# Power_supply.net
KiCad netlist of a schematic drawn in Altium Designer
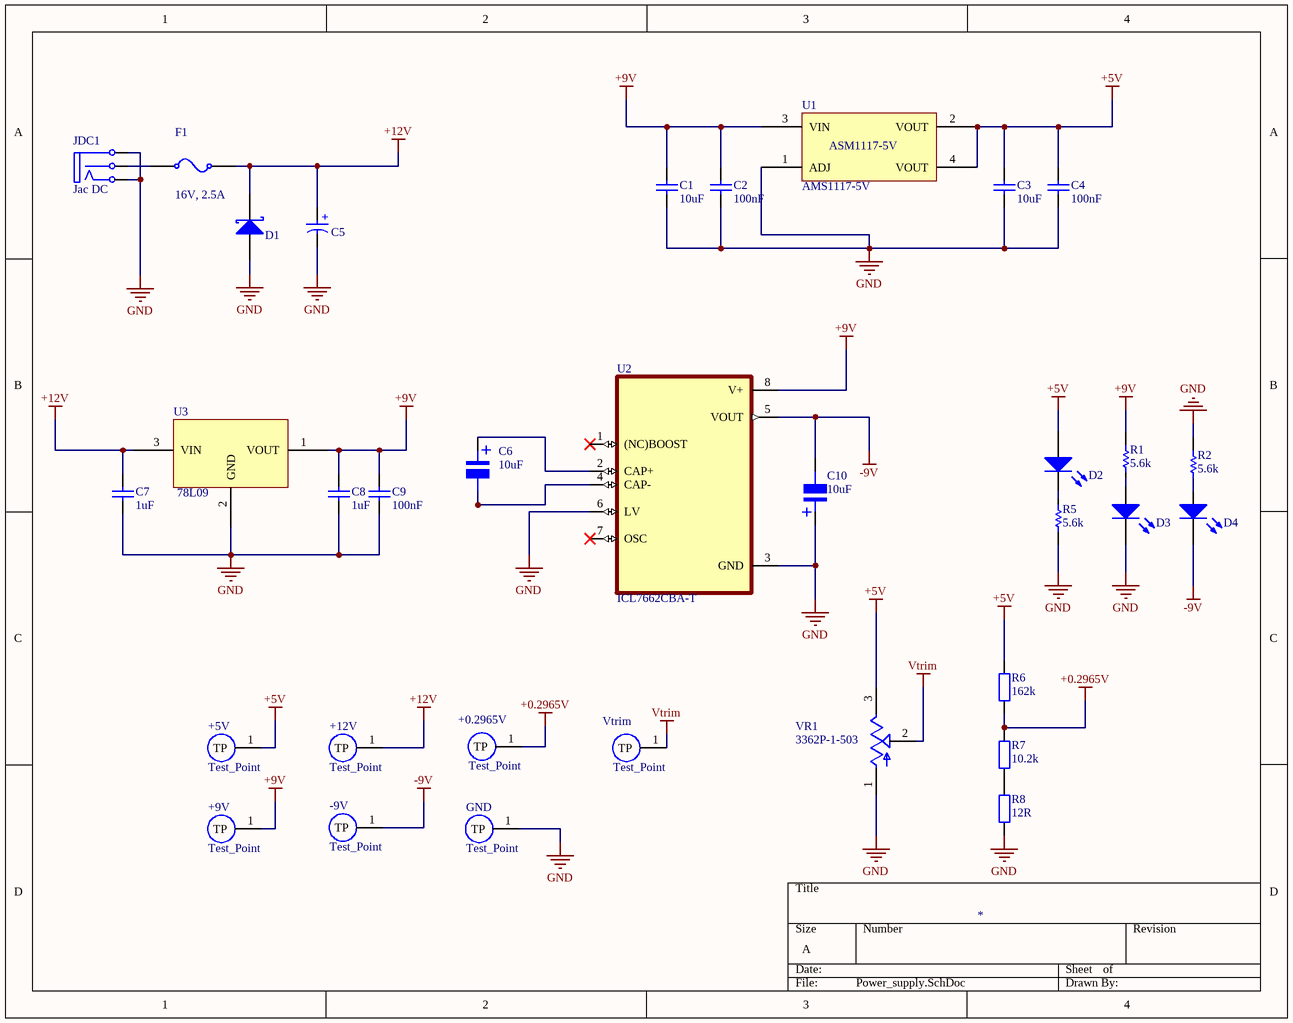
[diagram p0: Power_supply.SchDoc]

(export (version "E")
  (design (tool "Eeschema 10.0.6"))
  (components
    (comp (ref "+0.2965V")
      (value "Test_Point")
      (footprint "TP_2MM")
      (description "Test point, 2mm radius")
      (libsource (lib "SMIOT_Lib_Schematic") (part "Test_Point"))
    )
    (comp (ref "+5V")
      (value "Test_Point")
      (footprint "TP_2MM")
      (description "Test point, 2mm radius")
      (libsource (lib "SMIOT_Lib_Schematic") (part "Test_Point"))
    )
    (comp (ref "+9V")
      (value "Test_Point")
      (footprint "TP_2MM")
      (description "Test point, 2mm radius")
      (libsource (lib "SMIOT_Lib_Schematic") (part "Test_Point"))
    )
    (comp (ref "+12V")
      (value "Test_Point")
      (footprint "TP_2MM")
      (description "Test point, 2mm radius")
      (libsource (lib "SMIOT_Lib_Schematic") (part "Test_Point"))
    )
    (comp (ref "-9V")
      (value "Test_Point")
      (footprint "TP_2MM")
      (description "Test point, 2mm radius")
      (libsource (lib "SMIOT_Lib_Schematic") (part "Test_Point"))
    )
    (comp (ref "C1")
      (value "10uF")
      (footprint "CAP_0603")
      (description "CAP, size 0603,10uF")
      (libsource (lib "SMIOT_Lib_Schematic") (part "01060310010"))
    )
    (comp (ref "C2")
      (value "100nF")
      (footprint "CAP_0603")
      (description "CAP, size 0603, 100nF")
      (libsource (lib "SMIOT_Lib_Schematic") (part "01060310410"))
    )
    (comp (ref "C3")
      (value "10uF")
      (footprint "CAP_0603")
      (description "CAP, size 0603,10uF")
      (libsource (lib "SMIOT_Lib_Schematic") (part "01060310010"))
    )
    (comp (ref "C4")
      (value "100nF")
      (footprint "CAP_0603")
      (description "CAP, size 0603, 100nF")
      (libsource (lib "SMIOT_Lib_Schematic") (part "01060310410"))
    )
    (comp (ref "C5")
      (value "22uF")
      (footprint "WCAP-ASLI_D4H5.5")
      (description "V-Chip, D4 x H5.5mm, 22uF, 16V")
      (libsource (lib "SMIOT_Lib_Schematic") (part "865080340003"))
    )
    (comp (ref "C6")
      (value "10uF")
      (footprint "tu nhom 4 (b)")
      (description "Dán")
      (libsource (lib "") (part "Tu Nhom 10uF 16V_1"))
    )
    (comp (ref "C7")
      (value "1uF")
      (footprint "CAP_0603")
      (description "CAP, size 0603, 1uF")
      (libsource (lib "SMIOT_Lib_Schematic") (part "01060310510"))
    )
    (comp (ref "C8")
      (value "1uF")
      (footprint "CAP_0603")
      (description "CAP, size 0603, 1uF")
      (libsource (lib "SMIOT_Lib_Schematic") (part "01060310510"))
    )
    (comp (ref "C9")
      (value "100nF")
      (footprint "CAP_0603")
      (description "CAP, size 0603, 100nF")
      (libsource (lib "SMIOT_Lib_Schematic") (part "01060310410"))
    )
    (comp (ref "C10")
      (value "10uF")
      (footprint "tu nhom 4 (b)")
      (description "Dán")
      (libsource (lib "Tu dien") (part "Tu Nhom 10uF 16V"))
    )
    (comp (ref "D1")
      (value "D Schottky")
      (footprint "SS34")
      (description "Schottky Diode")
      (fields (field (name "PUBLISHER") "Altium Limited"))
      (libsource (lib "SMIOT_Lib_Schematic") (part "D Schottky"))
    )
    (comp (ref "D2")
      (value "LED SMD")
      (footprint "LED_0805_Blue")
      (description "LED")
      (libsource (lib "SMIOT_Lib_Schematic") (part "LED SMD"))
    )
    (comp (ref "D3")
      (value "LED SMD")
      (footprint "LED_0805_Blue")
      (description "LED")
      (libsource (lib "SMIOT_Lib_Schematic") (part "LED SMD"))
    )
    (comp (ref "D4")
      (value "LED SMD")
      (footprint "LED_0805_Blue")
      (description "LED")
      (libsource (lib "SMIOT_Lib_Schematic") (part "LED SMD"))
    )
    (comp (ref "F1")
      (value "16V, 2.5A")
      (footprint "Fuse_SMD_1812")
      (description "Resettable Fuse, Size 1812, 8V, 2A")
      (fields (field (name "MANUFACTURER") "Littelfuse"))
      (libsource (lib "SMIOT_Lib_Schematic") (part "061812200008"))
    )
    (comp (ref "GND")
      (value "Test_Point")
      (footprint "TP_2MM")
      (description "Test point, 2mm radius")
      (libsource (lib "SMIOT_Lib_Schematic") (part "Test_Point"))
    )
    (comp (ref "JDC1")
      (value "Jac DC")
      (footprint "DC0")
      (description "Jac DC input")
      (libsource (lib "Library") (part "DCIN"))
    )
    (comp (ref "R1")
      (value "5.6k")
      (footprint "resistor_0603")
      (description "RES, 5.6k Ohm, size 0603, 1%")
      (libsource (lib "SMIOT_Lib_Schematic") (part "0006035621"))
    )
    (comp (ref "R2")
      (value "5.6k")
      (footprint "resistor_0603")
      (description "RES, 5.6k Ohm, size 0603, 1%")
      (libsource (lib "SMIOT_Lib_Schematic") (part "0006035621"))
    )
    (comp (ref "R5")
      (value "5.6k")
      (footprint "resistor_0603")
      (description "RES, 5.6k Ohm, size 0603, 1%")
      (libsource (lib "SMIOT_Lib_Schematic") (part "0006035621"))
    )
    (comp (ref "R6")
      (value "162k")
      (footprint "TRO SMD 0603")
      (description "Dán")
      (libsource (lib "Dien Tro") (part "Tro 0603 1% 162k"))
    )
    (comp (ref "R7")
      (value "10.2k")
      (footprint "TRO SMD 0603")
      (description "Dán")
      (libsource (lib "Dien Tro") (part "tro 0603 1% 10.2k"))
    )
    (comp (ref "R8")
      (value "12R")
      (footprint "TRO SMD 0603")
      (description "Dán")
      (libsource (lib "Dien Tro") (part "tro 0805 1% 12R"))
    )
    (comp (ref "U1")
      (value "AMS1117-5V")
      (footprint "AMS1117-3.3V SOT223")
      (description "AMS1117-5V, OUT 5V 1A.")
      (libsource (lib "SMIOT_Lib_Schematic") (part "AMS1117-5V"))
    )
    (comp (ref "U2")
      (value "ICL7662CBA-T")
      (footprint "SOP 8")
      (fields
        (field (name "MF") "{'manufacturer': u'Analog Devices Inc./Maxim Integrated'}")
        (field (name "MP") "ICL7662CBA+T")
      )
      (libsource (lib "ICL7662CBA-T") (part "ICL7662CBA-T"))
    )
    (comp (ref "U3")
      (value "78L09")
      (footprint "SOT89")
      (description "78L09, OUT 9V, 0.1A")
      (libsource (lib "SMIOT_Lib_Schematic") (part "78L09"))
    )
    (comp (ref "VR1")
      (value "3362P-1-503")
      (footprint "TRIM_3362P-1-503")
      (description "50 kOhms 0.5W, 1/2W PC Pins Through Hole Trimmer Potentiometer Cermet 1 Turn Top Finger Adjustment")
      (fields (field (name "MF") "Bourns"))
      (libsource (lib "3362P-1-503") (part "3362P-1-503"))
    )
    (comp (ref "Vtrim")
      (value "Test_Point")
      (footprint "TP_2MM")
      (description "Test point, 2mm radius")
      (libsource (lib "SMIOT_Lib_Schematic") (part "Test_Point"))
    )
  )
  (nets
    (net (code "1") (name "+0.2965V") (class "Default")
      (node (ref "+0.2965V") (pin "1") (pinfunction "TP_1") (pintype "passive"))
      (node (ref "R6") (pin "1") (pintype "passive"))
      (node (ref "R7") (pin "2") (pintype "passive"))
    )
    (net (code "2") (name "+5V") (class "Default")
      (node (ref "+5V") (pin "1") (pinfunction "TP_1") (pintype "passive"))
      (node (ref "C3") (pin "2") (pinfunction "2_2") (pintype "passive"))
      (node (ref "C4") (pin "2") (pinfunction "2_2") (pintype "passive"))
      (node (ref "D2") (pin "1") (pinfunction "A_1") (pintype "passive"))
      (node (ref "R6") (pin "2") (pintype "passive"))
      (node (ref "U1") (pin "2") (pinfunction "VOUT_2") (pintype "passive"))
      (node (ref "U1") (pin "4") (pinfunction "VOUT_4") (pintype "power_in"))
      (node (ref "VR1") (pin "3") (pinfunction "CW_3") (pintype "passive"))
    )
    (net (code "3") (name "+9V") (class "Default")
      (node (ref "+9V") (pin "1") (pinfunction "TP_1") (pintype "passive"))
      (node (ref "C1") (pin "1") (pinfunction "1_1") (pintype "passive"))
      (node (ref "C2") (pin "2") (pinfunction "2_2") (pintype "passive"))
      (node (ref "C8") (pin "2") (pinfunction "2_2") (pintype "passive"))
      (node (ref "C9") (pin "2") (pinfunction "2_2") (pintype "passive"))
      (node (ref "R1") (pin "2") (pinfunction "2_2") (pintype "passive"))
      (node (ref "U1") (pin "3") (pinfunction "VIN_3") (pintype "passive"))
      (node (ref "U2") (pin "8") (pinfunction "V+_8") (pintype "power_in"))
      (node (ref "U3") (pin "1") (pinfunction "VOUT_1") (pintype "passive"))
    )
    (net (code "4") (name "+12V") (class "Default")
      (node (ref "+12V") (pin "1") (pinfunction "TP_1") (pintype "passive"))
      (node (ref "C5") (pin "1") (pinfunction "P_1") (pintype "passive"))
      (node (ref "C7") (pin "2") (pinfunction "2_2") (pintype "passive"))
      (node (ref "D1") (pin "2") (pinfunction "K_2") (pintype "passive"))
      (node (ref "F1") (pin "1") (pinfunction "1_1") (pintype "passive"))
      (node (ref "U3") (pin "3") (pinfunction "VIN_3") (pintype "passive"))
    )
    (net (code "5") (name "-9V") (class "Default")
      (node (ref "-9V") (pin "1") (pinfunction "TP_1") (pintype "passive"))
      (node (ref "C10") (pin "2") (pinfunction "2_2") (pintype "passive"))
      (node (ref "D4") (pin "2") (pinfunction "K_2") (pintype "passive"))
      (node (ref "U2") (pin "5") (pinfunction "VOUT_5") (pintype "output"))
    )
    (net (code "6") (name "GND") (class "Default")
      (node (ref "C1") (pin "2") (pinfunction "2_2") (pintype "passive"))
      (node (ref "C10") (pin "1") (pinfunction "1_1") (pintype "passive"))
      (node (ref "C2") (pin "1") (pinfunction "1_1") (pintype "passive"))
      (node (ref "C3") (pin "1") (pinfunction "1_1") (pintype "passive"))
      (node (ref "C4") (pin "1") (pinfunction "1_1") (pintype "passive"))
      (node (ref "C5") (pin "2") (pinfunction "N_2") (pintype "passive"))
      (node (ref "C7") (pin "1") (pinfunction "1_1") (pintype "passive"))
      (node (ref "C8") (pin "1") (pinfunction "1_1") (pintype "passive"))
      (node (ref "C9") (pin "1") (pinfunction "1_1") (pintype "passive"))
      (node (ref "D1") (pin "1") (pinfunction "A_1") (pintype "passive"))
      (node (ref "D3") (pin "2") (pinfunction "K_2") (pintype "passive"))
      (node (ref "GND") (pin "1") (pinfunction "TP_1") (pintype "passive"))
      (node (ref "JDC1") (pin "2") (pinfunction "TN_2") (pintype "passive"))
      (node (ref "JDC1") (pin "3") (pinfunction "T_3") (pintype "passive"))
      (node (ref "R2") (pin "2") (pinfunction "2_2") (pintype "passive"))
      (node (ref "R5") (pin "1") (pinfunction "1_1") (pintype "passive"))
      (node (ref "R8") (pin "1") (pinfunction "1_1") (pintype "passive"))
      (node (ref "U1") (pin "1") (pinfunction "ADJ_1") (pintype "power_in"))
      (node (ref "U2") (pin "3") (pinfunction "GND_3") (pintype "power_in"))
      (node (ref "U2") (pin "6") (pinfunction "LV_6") (pintype "bidirectional"))
      (node (ref "U3") (pin "2") (pinfunction "GND_2") (pintype "passive"))
      (node (ref "VR1") (pin "1") (pinfunction "CCW_1") (pintype "passive"))
    )
    (net (code "7") (name "Net-(D2-K)") (class "Default")
      (node (ref "D2") (pin "2") (pinfunction "K_2") (pintype "passive"))
      (node (ref "R5") (pin "2") (pinfunction "2_2") (pintype "passive"))
    )
    (net (code "8") (name "Net-(D3-A)") (class "Default")
      (node (ref "D3") (pin "1") (pinfunction "A_1") (pintype "passive"))
      (node (ref "R1") (pin "1") (pinfunction "1_1") (pintype "passive"))
    )
    (net (code "9") (name "Net-(D4-A)") (class "Default")
      (node (ref "D4") (pin "1") (pinfunction "A_1") (pintype "passive"))
      (node (ref "R2") (pin "1") (pinfunction "1_1") (pintype "passive"))
    )
    (net (code "10") (name "Net-(JDC1-S)") (class "Default")
      (node (ref "F1") (pin "0") (pinfunction "0_0") (pintype "passive"))
      (node (ref "JDC1") (pin "1") (pinfunction "S_1") (pintype "power_in"))
    )
    (net (code "11") (name "Net-(R7-Pad1)") (class "Default")
      (node (ref "R7") (pin "1") (pintype "passive"))
      (node (ref "R8") (pin "2") (pinfunction "2_2") (pintype "passive"))
    )
    (net (code "12") (name "Net-(U2-CAP+)") (class "Default")
      (node (ref "C6") (pin "1") (pinfunction "1_1") (pintype "passive"))
      (node (ref "U2") (pin "2") (pinfunction "CAP+_2") (pintype "bidirectional"))
    )
    (net (code "13") (name "Net-(U2-CAP-)") (class "Default")
      (node (ref "C6") (pin "2") (pinfunction "2_2") (pintype "passive"))
      (node (ref "U2") (pin "4") (pinfunction "CAP-_4") (pintype "bidirectional"))
    )
    (net (code "14") (name "Vtrim") (class "Default")
      (node (ref "VR1") (pin "2") (pinfunction "WIPER_2") (pintype "passive"))
      (node (ref "Vtrim") (pin "1") (pinfunction "TP_1") (pintype "passive"))
    )
    (net (code "15") (name "unconnected-(U2-(NC)BOOST-Pad1)") (class "Default")
      (node (ref "U2") (pin "1") (pinfunction "(NC)BOOST_1") (pintype "bidirectional+no_connect"))
    )
    (net (code "16") (name "unconnected-(U2-OSC-Pad7)") (class "Default")
      (node (ref "U2") (pin "7") (pinfunction "OSC_7") (pintype "bidirectional+no_connect"))
    )
  )
)
